# LCmeter0-LCD-8pinlcd-PICCOMP.net
KiCad netlist of a schematic drawn in EAGLE
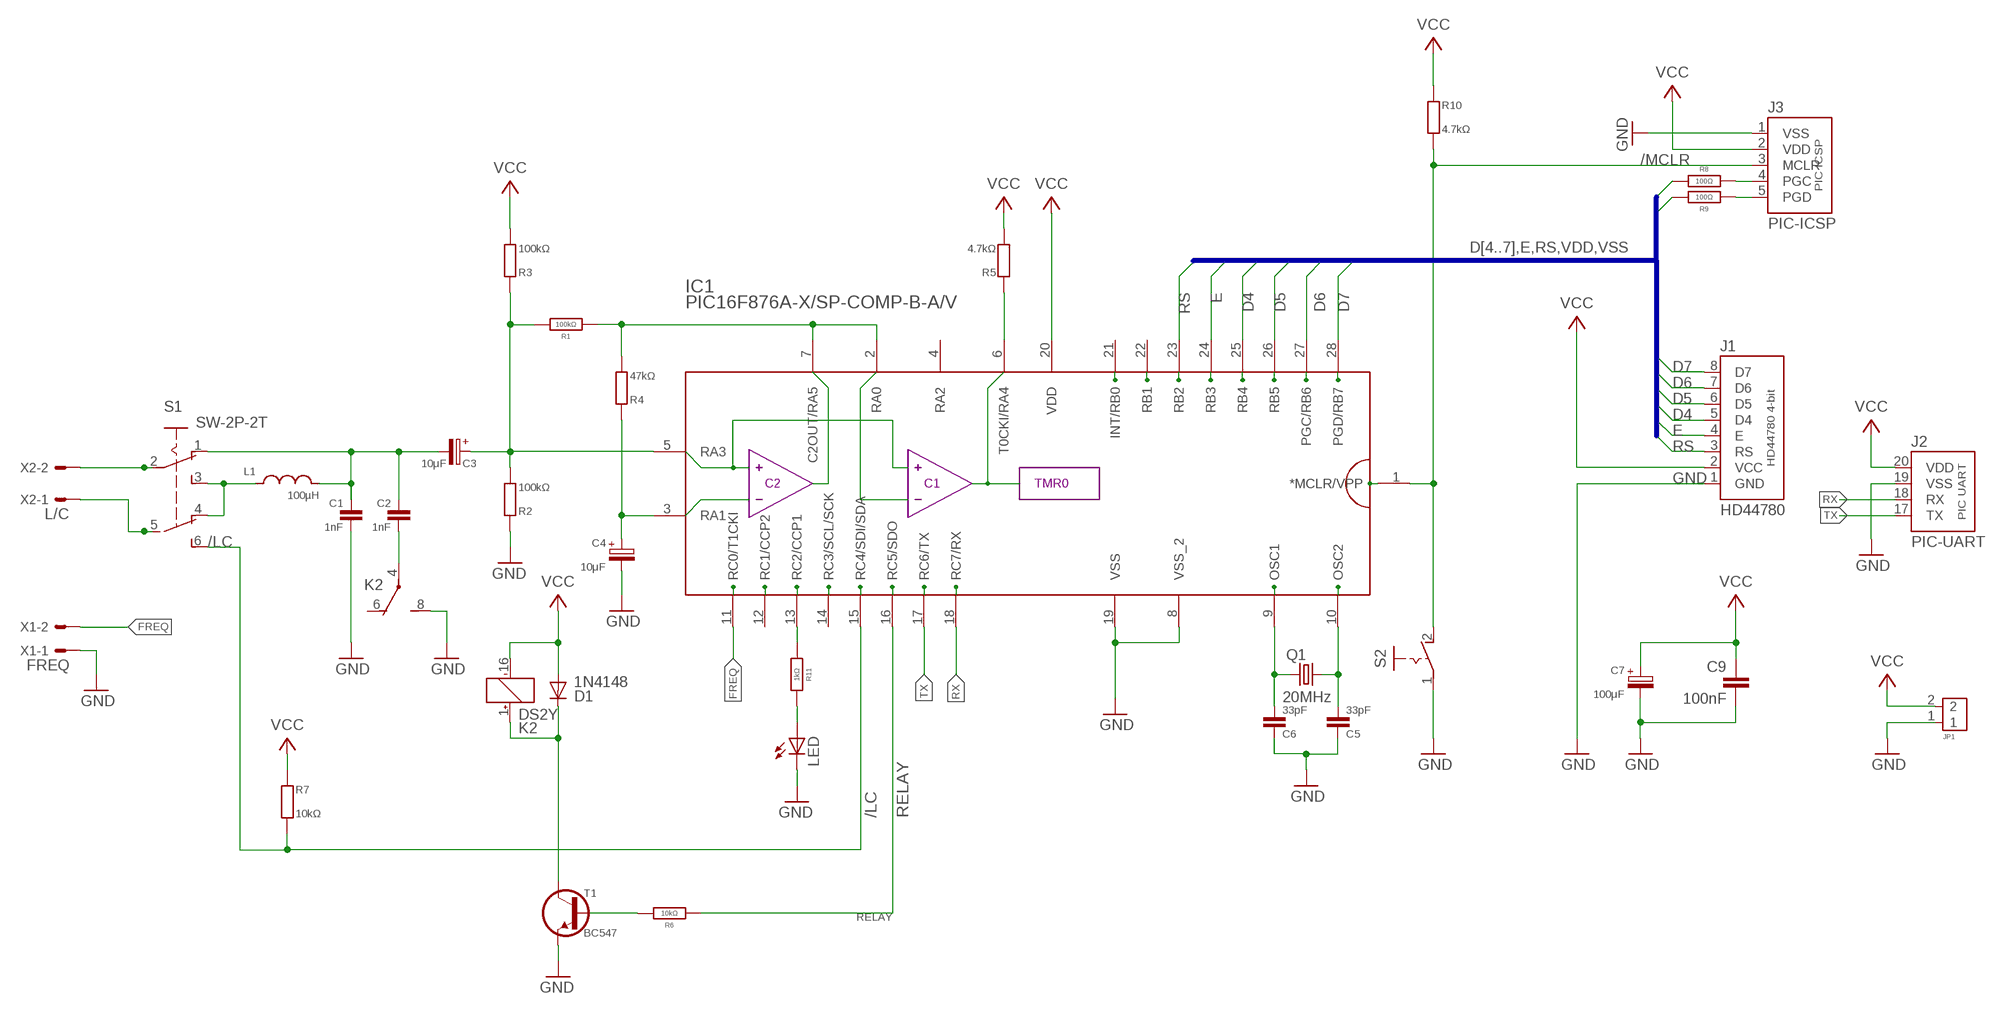
[diagram p0: schematic, sheet 1]

(export (version "E")
  (design (tool "Eeschema 10.0.6"))
  (components
    (comp (ref "C1")
      (value "1nF")
      (footprint "eagle-import:C050-020X036")
      (libsource (lib "eagle-import") (part "C050-020X036"))
    )
    (comp (ref "C2")
      (value "1nF")
      (footprint "eagle-import:C050-020X036")
      (libsource (lib "eagle-import") (part "C050-020X036"))
    )
    (comp (ref "C3")
      (value "10μF")
      (footprint "eagle-import:E2,5-4")
      (libsource (lib "eagle-import") (part "CPOL-HE2,5-4"))
    )
    (comp (ref "C4")
      (value "10μF")
      (footprint "eagle-import:E2,5-4")
      (libsource (lib "eagle-import") (part "CPOLE2,5-4"))
    )
    (comp (ref "C5")
      (value "33pF")
      (footprint "eagle-import:C025-020X036")
      (libsource (lib "eagle-import") (part "C025-020X036"))
    )
    (comp (ref "C6")
      (value "33pF")
      (footprint "eagle-import:C025-020X036")
      (libsource (lib "eagle-import") (part "C025-020X036"))
    )
    (comp (ref "C7")
      (value "100μF")
      (footprint "eagle-import:E2,5-5")
      (libsource (lib "eagle-import") (part "CPOLE2.5-5"))
    )
    (comp (ref "C9")
      (value "100nF")
      (footprint "eagle-import:C025-024X044")
      (libsource (lib "eagle-import") (part "C-EU025-024X044"))
    )
    (comp (ref "D1")
      (value "1N4148")
      (footprint "eagle-import:DO34-7")
      (libsource (lib "eagle-import") (part "1N414834-7"))
    )
    (comp (ref "IC1")
      (value "PIC16F876A-X/SP-COMP-B-A/V")
      (footprint "eagle-import:DIL28-3_V")
      (libsource (lib "eagle-import") (part "PIC16F876A-X/SP-COMP-B-A/V"))
    )
    (comp (ref "J1")
      (value "HD44780")
      (footprint "eagle-import:CONN-8P")
      (libsource (lib "eagle-import") (part "HD44780-4BIT-8PIN"))
    )
    (comp (ref "J2")
      (value "PIC-UART")
      (footprint "eagle-import:PIC-UART")
      (libsource (lib "eagle-import") (part "PIC-UART"))
    )
    (comp (ref "J3")
      (value "PIC-ICSP")
      (footprint "eagle-import:CONN-5P")
      (libsource (lib "eagle-import") (part "PIC-ICSP"))
    )
    (comp (ref "JP1")
      (value "CONN-2P2P/V")
      (footprint "eagle-import:CONN-2P-V")
      (libsource (lib "eagle-import") (part "CONN-2P2P/V"))
    )
    (comp (ref "K2")
      (value "DS2Y")
      (footprint "eagle-import:DS2Y")
      (fields (field (name "MPN") "DS2Y-S-DC5V"))
      (libsource (lib "eagle-import") (part "DS2Y-S-DC5V"))
    )
    (comp (ref "L1")
      (value "100µH")
      (footprint "eagle-import:L-02_7V")
      (libsource (lib "eagle-import") (part "L-SHORT02/7V"))
    )
    (comp (ref "LED")
      (value "TLLG4400")
      (footprint "eagle-import:LED3MM")
      (fields (field (name "MF") "VISHAY SEMICONDUCTOR"))
      (libsource (lib "eagle-import") (part "TLLG4400"))
    )
    (comp (ref "Q1")
      (value "20MHz")
      (footprint "eagle-import:HC49")
      (libsource (lib "eagle-import") (part "CRYSTALHC49"))
    )
    (comp (ref "R1")
      (value "100kΩ")
      (footprint "eagle-import:0204_10")
      (libsource (lib "eagle-import") (part "R-H0204/10"))
    )
    (comp (ref "R2")
      (value "100kΩ")
      (footprint "eagle-import:0204_10")
      (libsource (lib "eagle-import") (part "R0204/10"))
    )
    (comp (ref "R3")
      (value "100kΩ")
      (footprint "eagle-import:0204_10")
      (libsource (lib "eagle-import") (part "R0204/10"))
    )
    (comp (ref "R4")
      (value "47kΩ")
      (footprint "eagle-import:0204_10")
      (libsource (lib "eagle-import") (part "R0204/10"))
    )
    (comp (ref "R5")
      (value "4.7kΩ")
      (footprint "eagle-import:0204_10")
      (libsource (lib "eagle-import") (part "R0204/10"))
    )
    (comp (ref "R6")
      (value "10kΩ")
      (footprint "eagle-import:0204_10")
      (libsource (lib "eagle-import") (part "R-H0204/10"))
    )
    (comp (ref "R7")
      (value "10kΩ")
      (footprint "eagle-import:0204_10-V")
      (libsource (lib "eagle-import") (part "R0204/10-V"))
    )
    (comp (ref "R8")
      (value "100Ω")
      (footprint "eagle-import:0204_10")
      (libsource (lib "eagle-import") (part "R-H0204/10"))
    )
    (comp (ref "R9")
      (value "100Ω")
      (footprint "eagle-import:0204_10")
      (libsource (lib "eagle-import") (part "R-H0204/10"))
    )
    (comp (ref "R10")
      (value "4.7kΩ")
      (footprint "eagle-import:0204_10")
      (libsource (lib "eagle-import") (part "R0204/10"))
    )
    (comp (ref "R11")
      (value "1kΩ")
      (footprint "eagle-import:0204_10")
      (libsource (lib "eagle-import") (part "R-H0204/10"))
    )
    (comp (ref "S1")
      (value "SW-2P-2T")
      (footprint "eagle-import:SLSW-2P2T")
      (libsource (lib "eagle-import") (part "SW-2P-2T"))
    )
    (comp (ref "S2")
      (value "PB-1P-1T")
      (footprint "eagle-import:PB-1P1T")
      (libsource (lib "eagle-import") (part "PB-1P-1T"))
    )
    (comp (ref "T1")
      (value "BC547")
      (footprint "eagle-import:TO92-CBE")
      (libsource (lib "eagle-import") (part "BC547"))
    )
    (comp (ref "X1")
      (value "FREQ")
      (footprint "eagle-import:70543-02")
      (libsource (lib "eagle-import") (part "C-GRID-02-70543"))
    )
    (comp (ref "X2")
      (value "L/C")
      (footprint "eagle-import:70543-02")
      (libsource (lib "eagle-import") (part "C-GRID-02-70543"))
    )
  )
  (nets
    (net (code "3") (name "/D4") (class "Default")
      (node (ref "IC1") (pin "25") (pinfunction "RB4_25") (pintype "passive"))
      (node (ref "J1") (pin "5") (pinfunction "D4_5") (pintype "passive"))
    )
    (net (code "4") (name "/D5") (class "Default")
      (node (ref "IC1") (pin "26") (pinfunction "RB5_26") (pintype "passive"))
      (node (ref "J1") (pin "6") (pinfunction "D5_6") (pintype "passive"))
    )
    (net (code "5") (name "/D6") (class "Default")
      (node (ref "IC1") (pin "27") (pinfunction "PGC/RB6_27") (pintype "passive"))
      (node (ref "J1") (pin "7") (pinfunction "D6_7") (pintype "passive"))
      (node (ref "R9") (pin "1") (pinfunction "1_1") (pintype "passive"))
    )
    (net (code "6") (name "/D7") (class "Default")
      (node (ref "IC1") (pin "28") (pinfunction "PGD/RB7_28") (pintype "passive"))
      (node (ref "J1") (pin "8") (pinfunction "D7_8") (pintype "passive"))
      (node (ref "R8") (pin "1") (pinfunction "1_1") (pintype "passive"))
    )
    (net (code "7") (name "/E") (class "Default")
      (node (ref "IC1") (pin "24") (pinfunction "RB3_24") (pintype "passive"))
      (node (ref "J1") (pin "4") (pinfunction "E_4") (pintype "passive"))
    )
    (net (code "8") (name "/RELAY") (class "Default")
      (node (ref "IC1") (pin "16") (pinfunction "RC5/SDO_16") (pintype "passive"))
      (node (ref "R6") (pin "2") (pinfunction "2_2") (pintype "passive"))
    )
    (net (code "9") (name "/RS") (class "Default")
      (node (ref "IC1") (pin "23") (pinfunction "RB2_23") (pintype "passive"))
      (node (ref "J1") (pin "3") (pinfunction "RS_3") (pintype "passive"))
    )
    (net (code "11") (name "/{slash}LC") (class "Default")
      (node (ref "IC1") (pin "15") (pinfunction "RC4/SDI/SDA_15") (pintype "passive"))
      (node (ref "R7") (pin "2") (pinfunction "1_2") (pintype "passive"))
      (node (ref "S1") (pin "6") (pinfunction "S1_6") (pintype "passive"))
    )
    (net (code "12") (name "/{slash}MCLR") (class "Default")
      (node (ref "IC1") (pin "1") (pinfunction "*MCLR/VPP_1") (pintype "passive"))
      (node (ref "J3") (pin "3") (pinfunction "MCLR_3") (pintype "passive"))
      (node (ref "R10") (pin "2") (pinfunction "1_2") (pintype "passive"))
      (node (ref "S2") (pin "2") (pinfunction "S_2") (pintype "passive"))
    )
    (net (code "13") (name "FREQ") (class "Default")
      (node (ref "IC1") (pin "11") (pinfunction "RC0/T1CKI_11") (pintype "passive"))
      (node (ref "X1") (pin "2") (pinfunction "S_2") (pintype "passive"))
    )
    (net (code "14") (name "GND") (class "Default")
      (node (ref "C1") (pin "2") (pinfunction "2_2") (pintype "passive"))
      (node (ref "C4") (pin "-") (pinfunction "-_-") (pintype "passive"))
      (node (ref "C5") (pin "1") (pinfunction "1_1") (pintype "passive"))
      (node (ref "C6") (pin "1") (pinfunction "1_1") (pintype "passive"))
      (node (ref "C7") (pin "-") (pinfunction "-_-") (pintype "passive"))
      (node (ref "C9") (pin "2") (pinfunction "2_2") (pintype "passive"))
      (node (ref "IC1") (pin "19") (pinfunction "VSS_19") (pintype "passive"))
      (node (ref "IC1") (pin "8") (pinfunction "VSS_2_8") (pintype "passive"))
      (node (ref "J1") (pin "1") (pinfunction "GND_1") (pintype "passive"))
      (node (ref "J2") (pin "19") (pinfunction "VSS_19") (pintype "passive"))
      (node (ref "J3") (pin "1") (pinfunction "VSS_1") (pintype "passive"))
      (node (ref "JP1") (pin "1") (pinfunction "1_1") (pintype "bidirectional"))
      (node (ref "K2") (pin "8") (pinfunction "S_8") (pintype "passive"))
      (node (ref "LED") (pin "K") (pinfunction "C_K") (pintype "passive"))
      (node (ref "R2") (pin "1") (pinfunction "2_1") (pintype "passive"))
      (node (ref "S2") (pin "1") (pinfunction "P_1") (pintype "passive"))
      (node (ref "T1") (pin "E") (pinfunction "E_E") (pintype "passive"))
      (node (ref "X1") (pin "1") (pinfunction "S_1") (pintype "passive"))
    )
    (net (code "15") (name "Net-(IC1-C2OUT{slash}RA5)") (class "Default")
      (node (ref "IC1") (pin "2") (pinfunction "RA0_2") (pintype "passive"))
      (node (ref "IC1") (pin "7") (pinfunction "C2OUT/RA5_7") (pintype "passive"))
      (node (ref "R1") (pin "1") (pinfunction "1_1") (pintype "passive"))
      (node (ref "R4") (pin "2") (pinfunction "1_2") (pintype "passive"))
    )
    (net (code "16") (name "Net-(IC1-OSC1)") (class "Default")
      (node (ref "C6") (pin "2") (pinfunction "2_2") (pintype "passive"))
      (node (ref "IC1") (pin "9") (pinfunction "OSC1_9") (pintype "passive"))
      (node (ref "Q1") (pin "1") (pinfunction "1_1") (pintype "passive"))
    )
    (net (code "17") (name "Net-(IC1-OSC2)") (class "Default")
      (node (ref "C5") (pin "2") (pinfunction "2_2") (pintype "passive"))
      (node (ref "IC1") (pin "10") (pinfunction "OSC2_10") (pintype "passive"))
      (node (ref "Q1") (pin "2") (pinfunction "2_2") (pintype "passive"))
    )
    (net (code "18") (name "Net-(IC1-RA1)") (class "Default")
      (node (ref "C4") (pin "+") (pinfunction "+_+") (pintype "passive"))
      (node (ref "IC1") (pin "3") (pinfunction "RA1_3") (pintype "passive"))
      (node (ref "R4") (pin "1") (pinfunction "2_1") (pintype "passive"))
    )
    (net (code "19") (name "Net-(IC1-RA3)") (class "Default")
      (node (ref "C3") (pin "+") (pinfunction "+_+") (pintype "passive"))
      (node (ref "IC1") (pin "5") (pinfunction "RA3_5") (pintype "passive"))
      (node (ref "R1") (pin "2") (pinfunction "2_2") (pintype "passive"))
      (node (ref "R2") (pin "2") (pinfunction "1_2") (pintype "passive"))
      (node (ref "R3") (pin "1") (pinfunction "2_1") (pintype "passive"))
    )
    (net (code "20") (name "Net-(IC1-RC2{slash}CCP1)") (class "Default")
      (node (ref "IC1") (pin "13") (pinfunction "RC2/CCP1_13") (pintype "passive"))
      (node (ref "R11") (pin "2") (pinfunction "2_2") (pintype "passive"))
    )
    (net (code "21") (name "Net-(IC1-T0CKI{slash}RA4)") (class "Default")
      (node (ref "IC1") (pin "6") (pinfunction "T0CKI/RA4_6") (pintype "passive"))
      (node (ref "R5") (pin "1") (pinfunction "2_1") (pintype "passive"))
    )
    (net (code "22") (name "Net-(J3-PGC)") (class "Default")
      (node (ref "J3") (pin "4") (pinfunction "PGC_4") (pintype "passive"))
      (node (ref "R8") (pin "2") (pinfunction "2_2") (pintype "passive"))
    )
    (net (code "23") (name "Net-(J3-PGD)") (class "Default")
      (node (ref "J3") (pin "5") (pinfunction "PGD_5") (pintype "passive"))
      (node (ref "R9") (pin "2") (pinfunction "2_2") (pintype "passive"))
    )
    (net (code "24") (name "Net-(K2A-+)") (class "Default")
      (node (ref "D1") (pin "C") (pinfunction "C_C") (pintype "passive"))
      (node (ref "K2") (pin "1") (pinfunction "+_1") (pintype "passive"))
      (node (ref "T1") (pin "C") (pinfunction "C_C") (pintype "passive"))
    )
    (net (code "25") (name "Net-(K2B-P)") (class "Default")
      (node (ref "C2") (pin "2") (pinfunction "2_2") (pintype "passive"))
      (node (ref "K2") (pin "4") (pinfunction "P_4") (pintype "passive"))
    )
    (net (code "26") (name "Net-(LED-PadA)") (class "Default")
      (node (ref "LED") (pin "A") (pinfunction "A_A") (pintype "passive"))
      (node (ref "R11") (pin "1") (pinfunction "1_1") (pintype "passive"))
    )
    (net (code "27") (name "Net-(R6-Pad1)") (class "Default")
      (node (ref "R6") (pin "1") (pinfunction "1_1") (pintype "passive"))
      (node (ref "T1") (pin "B") (pinfunction "B_B") (pintype "passive"))
    )
    (net (code "28") (name "Net-(S1-O)") (class "Default")
      (node (ref "C1") (pin "1") (pinfunction "1_1") (pintype "passive"))
      (node (ref "C2") (pin "1") (pinfunction "1_1") (pintype "passive"))
      (node (ref "C3") (pin "-") (pinfunction "-_-") (pintype "passive"))
      (node (ref "L1") (pin "2") (pinfunction "2_2") (pintype "passive"))
      (node (ref "S1") (pin "1") (pinfunction "O_1") (pintype "passive"))
    )
    (net (code "29") (name "Net-(S1-O1)") (class "Default")
      (node (ref "L1") (pin "1") (pinfunction "1_1") (pintype "passive"))
      (node (ref "S1") (pin "3") (pinfunction "S_3") (pintype "passive"))
      (node (ref "S1") (pin "4") (pinfunction "O1_4") (pintype "passive"))
    )
    (net (code "30") (name "Net-(S1-P)") (class "Default")
      (node (ref "S1") (pin "2") (pinfunction "P_2") (pintype "passive"))
      (node (ref "X2") (pin "2") (pinfunction "S_2") (pintype "passive"))
    )
    (net (code "31") (name "Net-(S1-P1)") (class "Default")
      (node (ref "S1") (pin "5") (pinfunction "P1_5") (pintype "passive"))
      (node (ref "X2") (pin "1") (pinfunction "S_1") (pintype "passive"))
    )
    (net (code "32") (name "RX") (class "Default")
      (node (ref "IC1") (pin "18") (pinfunction "RC7/RX_18") (pintype "passive"))
      (node (ref "J2") (pin "18") (pinfunction "RX_18") (pintype "passive"))
    )
    (net (code "33") (name "TX") (class "Default")
      (node (ref "IC1") (pin "17") (pinfunction "RC6/TX_17") (pintype "passive"))
      (node (ref "J2") (pin "17") (pinfunction "TX_17") (pintype "passive"))
    )
    (net (code "34") (name "VCC") (class "Default")
      (node (ref "C7") (pin "+") (pinfunction "+_+") (pintype "passive"))
      (node (ref "C9") (pin "1") (pinfunction "1_1") (pintype "passive"))
      (node (ref "D1") (pin "A") (pinfunction "A_A") (pintype "passive"))
      (node (ref "IC1") (pin "20") (pinfunction "VDD_20") (pintype "passive"))
      (node (ref "J1") (pin "2") (pinfunction "VCC_2") (pintype "passive"))
      (node (ref "J2") (pin "20") (pinfunction "VDD_20") (pintype "passive"))
      (node (ref "J3") (pin "2") (pinfunction "VDD_2") (pintype "passive"))
      (node (ref "JP1") (pin "2") (pinfunction "2_2") (pintype "bidirectional"))
      (node (ref "K2") (pin "16") (pinfunction "-_16") (pintype "passive"))
      (node (ref "R10") (pin "1") (pinfunction "2_1") (pintype "passive"))
      (node (ref "R3") (pin "2") (pinfunction "1_2") (pintype "passive"))
      (node (ref "R5") (pin "2") (pinfunction "1_2") (pintype "passive"))
      (node (ref "R7") (pin "1") (pinfunction "2_1") (pintype "passive"))
    )
    (net (code "35") (name "unconnected-(IC1-INT{slash}RB0-Pad21)") (class "Default")
      (node (ref "IC1") (pin "21") (pinfunction "INT/RB0_21") (pintype "passive"))
    )
    (net (code "36") (name "unconnected-(IC1-RA2-Pad4)") (class "Default")
      (node (ref "IC1") (pin "4") (pinfunction "RA2_4") (pintype "passive"))
    )
    (net (code "37") (name "unconnected-(IC1-RB1-Pad22)") (class "Default")
      (node (ref "IC1") (pin "22") (pinfunction "RB1_22") (pintype "passive"))
    )
    (net (code "38") (name "unconnected-(IC1-RC1{slash}CCP2-Pad12)") (class "Default")
      (node (ref "IC1") (pin "12") (pinfunction "RC1/CCP2_12") (pintype "passive"))
    )
    (net (code "39") (name "unconnected-(IC1-RC3{slash}SCL{slash}SCK-Pad14)") (class "Default")
      (node (ref "IC1") (pin "14") (pinfunction "RC3/SCL/SCK_14") (pintype "passive"))
    )
    (net (code "40") (name "unconnected-(K2B-O-Pad6)") (class "Default")
      (node (ref "K2") (pin "6") (pinfunction "O_6") (pintype "passive"))
    )
  )
)
